# SANE_v1.net
KiCad netlist of a schematic drawn in EAGLE
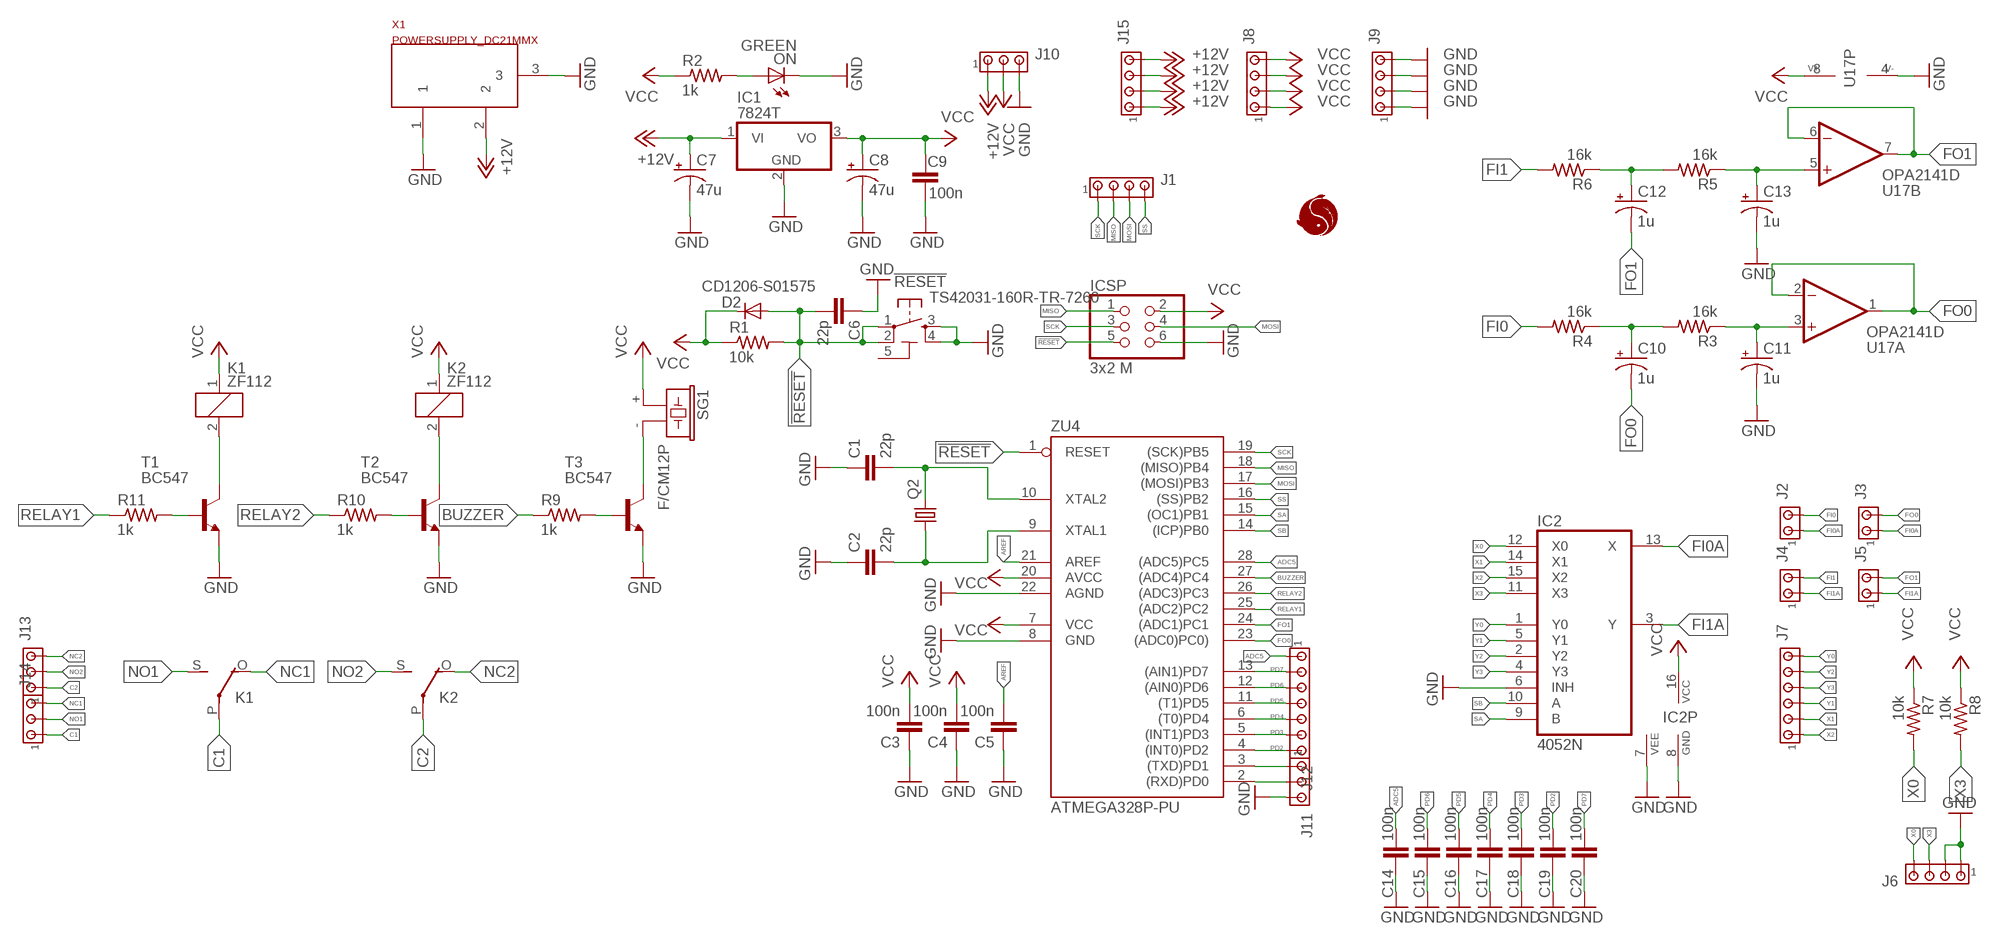
[diagram p0: schematic, sheet 1]

(export (version "E")
  (design (tool "Eeschema 10.0.6"))
  (components
    (comp (ref "!RESET")
      (value "TS42031-160R-TR-7260")
      (footprint "eagle-import:TS42")
      (libsource (lib "eagle-import") (part "TS42"))
    )
    (comp (ref "C1")
      (value "22p")
      (footprint "eagle-import:C0805")
      (libsource (lib "eagle-import") (part "C-EUC0805"))
    )
    (comp (ref "C2")
      (value "22p")
      (footprint "eagle-import:C0805")
      (libsource (lib "eagle-import") (part "C-EUC0805"))
    )
    (comp (ref "C3")
      (value "100n")
      (footprint "eagle-import:C0805")
      (libsource (lib "eagle-import") (part "C-EUC0805"))
    )
    (comp (ref "C4")
      (value "100n")
      (footprint "eagle-import:C0805")
      (libsource (lib "eagle-import") (part "C-EUC0805"))
    )
    (comp (ref "C5")
      (value "100n")
      (footprint "eagle-import:C0805")
      (libsource (lib "eagle-import") (part "C-EUC0805"))
    )
    (comp (ref "C6")
      (value "22p")
      (footprint "eagle-import:C0805")
      (libsource (lib "eagle-import") (part "C-EUC0805"))
    )
    (comp (ref "C7")
      (value "47u")
      (footprint "eagle-import:E2-4")
      (libsource (lib "eagle-import") (part "CPOL-USE2-4"))
    )
    (comp (ref "C8")
      (value "47u")
      (footprint "eagle-import:E2-4")
      (libsource (lib "eagle-import") (part "CPOL-USE2-4"))
    )
    (comp (ref "C9")
      (value "100n")
      (footprint "eagle-import:C0805")
      (libsource (lib "eagle-import") (part "C-EUC0805"))
    )
    (comp (ref "C10")
      (value "1u")
      (footprint "eagle-import:E2-4")
      (libsource (lib "eagle-import") (part "CPOL-USE2-4"))
    )
    (comp (ref "C11")
      (value "1u")
      (footprint "eagle-import:E2-4")
      (libsource (lib "eagle-import") (part "CPOL-USE2-4"))
    )
    (comp (ref "C12")
      (value "1u")
      (footprint "eagle-import:E2-4")
      (libsource (lib "eagle-import") (part "CPOL-USE2-4"))
    )
    (comp (ref "C13")
      (value "1u")
      (footprint "eagle-import:E2-4")
      (libsource (lib "eagle-import") (part "CPOL-USE2-4"))
    )
    (comp (ref "C14")
      (value "100n")
      (footprint "eagle-import:C0805")
      (libsource (lib "eagle-import") (part "C-EUC0805"))
    )
    (comp (ref "C15")
      (value "100n")
      (footprint "eagle-import:C0805")
      (libsource (lib "eagle-import") (part "C-EUC0805"))
    )
    (comp (ref "C16")
      (value "100n")
      (footprint "eagle-import:C0805")
      (libsource (lib "eagle-import") (part "C-EUC0805"))
    )
    (comp (ref "C17")
      (value "100n")
      (footprint "eagle-import:C0805")
      (libsource (lib "eagle-import") (part "C-EUC0805"))
    )
    (comp (ref "C18")
      (value "100n")
      (footprint "eagle-import:C0805")
      (libsource (lib "eagle-import") (part "C-EUC0805"))
    )
    (comp (ref "C19")
      (value "100n")
      (footprint "eagle-import:C0805")
      (libsource (lib "eagle-import") (part "C-EUC0805"))
    )
    (comp (ref "C20")
      (value "100n")
      (footprint "eagle-import:C0805")
      (libsource (lib "eagle-import") (part "C-EUC0805"))
    )
    (comp (ref "D2")
      (value "CD1206-S01575")
      (footprint "eagle-import:MINIMELF")
      (libsource (lib "eagle-import") (part "DIODE-MINIMELF"))
    )
    (comp (ref "IC1")
      (value "7824T")
      (footprint "eagle-import:TO220H")
      (libsource (lib "eagle-import") (part "78T24"))
    )
    (comp (ref "IC2")
      (value "4052N")
      (footprint "eagle-import:DIL16")
      (libsource (lib "eagle-import") (part "4052N"))
    )
    (comp (ref "ICSP")
      (value "3x2 M")
      (footprint "eagle-import:2X03")
      (libsource (lib "eagle-import") (part "PINHD-2X3"))
    )
    (comp (ref "J1")
      (value "MTA04-100")
      (footprint "eagle-import:10X04MTA")
      (libsource (lib "eagle-import") (part "MTA04-100"))
    )
    (comp (ref "J2")
      (value "MTA02-100")
      (footprint "eagle-import:10X02MTA")
      (libsource (lib "eagle-import") (part "MTA02-100"))
    )
    (comp (ref "J3")
      (value "MTA02-100")
      (footprint "eagle-import:10X02MTA")
      (libsource (lib "eagle-import") (part "MTA02-100"))
    )
    (comp (ref "J4")
      (value "MTA02-100")
      (footprint "eagle-import:10X02MTA")
      (libsource (lib "eagle-import") (part "MTA02-100"))
    )
    (comp (ref "J5")
      (value "MTA02-100")
      (footprint "eagle-import:10X02MTA")
      (libsource (lib "eagle-import") (part "MTA02-100"))
    )
    (comp (ref "J6")
      (value "MTA04-100")
      (footprint "eagle-import:10X04MTA")
      (libsource (lib "eagle-import") (part "MTA04-100"))
    )
    (comp (ref "J7")
      (value "MTA06-100")
      (footprint "eagle-import:10X06MTA")
      (libsource (lib "eagle-import") (part "MTA06-100"))
    )
    (comp (ref "J8")
      (value "MTA04-100")
      (footprint "eagle-import:10X04MTA")
      (libsource (lib "eagle-import") (part "MTA04-100"))
    )
    (comp (ref "J9")
      (value "MTA04-100")
      (footprint "eagle-import:10X04MTA")
      (libsource (lib "eagle-import") (part "MTA04-100"))
    )
    (comp (ref "J10")
      (value "MTA03-100")
      (footprint "eagle-import:10X03MTA")
      (libsource (lib "eagle-import") (part "MTA03-100"))
    )
    (comp (ref "J11")
      (value "MTA03-100")
      (footprint "eagle-import:10X03MTA")
      (libsource (lib "eagle-import") (part "MTA03-100"))
    )
    (comp (ref "J12")
      (value "MTA07-100")
      (footprint "eagle-import:10X07MTA")
      (libsource (lib "eagle-import") (part "MTA07-100"))
    )
    (comp (ref "J13")
      (value "MTA03-156")
      (footprint "eagle-import:1X3MTA")
      (libsource (lib "eagle-import") (part "MTA03-156"))
    )
    (comp (ref "J14")
      (value "MTA03-156")
      (footprint "eagle-import:1X3MTA")
      (libsource (lib "eagle-import") (part "MTA03-156"))
    )
    (comp (ref "J15")
      (value "MTA04-100")
      (footprint "eagle-import:10X04MTA")
      (libsource (lib "eagle-import") (part "MTA04-100"))
    )
    (comp (ref "K1")
      (value "ZF112")
      (footprint "eagle-import:ZF112")
      (libsource (lib "eagle-import") (part "ZF112"))
    )
    (comp (ref "K2")
      (value "ZF112")
      (footprint "eagle-import:ZF112")
      (libsource (lib "eagle-import") (part "ZF112"))
    )
    (comp (ref "ON")
      (value "GREEN")
      (footprint "eagle-import:CHIP-LED0805")
      (libsource (lib "eagle-import") (part "LEDCHIP-LED0805"))
    )
    (comp (ref "Q2")
      (value "CRYSTALHC49U-V")
      (footprint "eagle-import:HC49U-V")
      (libsource (lib "eagle-import") (part "CRYSTALHC49U-V"))
    )
    (comp (ref "R1")
      (value "10k")
      (footprint "eagle-import:R0805")
      (libsource (lib "eagle-import") (part "R-US_R0805"))
    )
    (comp (ref "R2")
      (value "1k")
      (footprint "eagle-import:R0805")
      (libsource (lib "eagle-import") (part "R-US_R0805"))
    )
    (comp (ref "R3")
      (value "16k")
      (footprint "eagle-import:R0805")
      (libsource (lib "eagle-import") (part "R-US_R0805"))
    )
    (comp (ref "R4")
      (value "16k")
      (footprint "eagle-import:R0805")
      (libsource (lib "eagle-import") (part "R-US_R0805"))
    )
    (comp (ref "R5")
      (value "16k")
      (footprint "eagle-import:R0805")
      (libsource (lib "eagle-import") (part "R-US_R0805"))
    )
    (comp (ref "R6")
      (value "16k")
      (footprint "eagle-import:R0805")
      (libsource (lib "eagle-import") (part "R-US_R0805"))
    )
    (comp (ref "R7")
      (value "10k")
      (footprint "eagle-import:R0805")
      (libsource (lib "eagle-import") (part "R-US_R0805"))
    )
    (comp (ref "R8")
      (value "10k")
      (footprint "eagle-import:R0805")
      (libsource (lib "eagle-import") (part "R-US_R0805"))
    )
    (comp (ref "R9")
      (value "1k")
      (footprint "eagle-import:R0805")
      (libsource (lib "eagle-import") (part "R-US_R0805"))
    )
    (comp (ref "R10")
      (value "1k")
      (footprint "eagle-import:R0805")
      (libsource (lib "eagle-import") (part "R-US_R0805"))
    )
    (comp (ref "R11")
      (value "1k")
      (footprint "eagle-import:R0805")
      (libsource (lib "eagle-import") (part "R-US_R0805"))
    )
    (comp (ref "SG1")
      (value "F/CM12P")
      (footprint "eagle-import:F_CM12P")
      (libsource (lib "eagle-import") (part "F/CM12P"))
    )
    (comp (ref "T1")
      (value "BC547")
      (footprint "eagle-import:TO92")
      (libsource (lib "eagle-import") (part "BC547"))
    )
    (comp (ref "T2")
      (value "BC547")
      (footprint "eagle-import:TO92")
      (libsource (lib "eagle-import") (part "BC547"))
    )
    (comp (ref "T3")
      (value "BC547")
      (footprint "eagle-import:TO92")
      (libsource (lib "eagle-import") (part "BC547"))
    )
    (comp (ref "U$1")
      (value "LOGO-SANE")
      (footprint "eagle-import:LOGO-SANE")
      (libsource (lib "eagle-import") (part "LOGO-SANE"))
    )
    (comp (ref "U17")
      (value "OPA2141D")
      (footprint "eagle-import:SO08")
      (libsource (lib "eagle-import") (part "OPA2141D"))
    )
    (comp (ref "X1")
      (value "POWERSUPPLY_DC21MMX")
      (footprint "eagle-import:POWERSUPPLY_DC-21MM")
      (libsource (lib "eagle-import") (part "POWERSUPPLY_DC21MMX"))
    )
    (comp (ref "ZU4")
      (value "ATMEGA328P-PU")
      (footprint "eagle-import:DIL28-3")
      (libsource (lib "eagle-import") (part "ATMEGA328P-PU"))
    )
  )
  (nets
    (net (code "1") (name "+12V") (class "Default")
      (node (ref "C7") (pin "+") (pinfunction "+_+") (pintype "passive"))
      (node (ref "IC1") (pin "1") (pinfunction "VI_1") (pintype "input"))
      (node (ref "J10") (pin "1") (pinfunction "1_1") (pintype "passive"))
      (node (ref "J15") (pin "1") (pinfunction "1_1") (pintype "passive"))
      (node (ref "J15") (pin "2") (pinfunction "2_2") (pintype "passive"))
      (node (ref "J15") (pin "3") (pinfunction "3_3") (pintype "passive"))
      (node (ref "J15") (pin "4") (pinfunction "4_4") (pintype "passive"))
      (node (ref "X1") (pin "2") (pinfunction "2_2") (pintype "power_in"))
    )
    (net (code "2") (name "/5-GND") (class "Default")
      (node (ref "!RESET") (pin "5") (pinfunction "5-GND_5") (pintype "power_in"))
    )
    (net (code "3") (name "/~{RESET}") (class "Default")
      (node (ref "!RESET") (pin "1") (pinfunction "1_1") (pintype "passive"))
      (node (ref "!RESET") (pin "2") (pinfunction "2_2") (pintype "passive"))
      (node (ref "C6") (pin "2") (pinfunction "2_2") (pintype "passive"))
      (node (ref "D2") (pin "A") (pinfunction "A_A") (pintype "passive"))
      (node (ref "ICSP") (pin "5") (pinfunction "5_5") (pintype "passive"))
      (node (ref "R1") (pin "2") (pinfunction "2_2") (pintype "passive"))
      (node (ref "ZU4") (pin "1") (pinfunction "RESET_1") (pintype "input"))
    )
    (net (code "4") (name "ADC5") (class "Default")
      (node (ref "C14") (pin "2") (pinfunction "2_2") (pintype "passive"))
      (node (ref "J12") (pin "1") (pinfunction "1_1") (pintype "passive"))
      (node (ref "ZU4") (pin "28") (pinfunction "(ADC5)PC5_28") (pintype "bidirectional"))
    )
    (net (code "5") (name "AREF") (class "Default")
      (node (ref "C5") (pin "2") (pinfunction "2_2") (pintype "passive"))
      (node (ref "ZU4") (pin "21") (pinfunction "AREF_21") (pintype "passive"))
    )
    (net (code "6") (name "BUZZER") (class "Default")
      (node (ref "R9") (pin "1") (pinfunction "1_1") (pintype "passive"))
      (node (ref "ZU4") (pin "27") (pinfunction "(ADC4)PC4_27") (pintype "bidirectional"))
    )
    (net (code "7") (name "C1") (class "Default")
      (node (ref "J14") (pin "1") (pinfunction "1_1") (pintype "passive"))
      (node (ref "K1") (pin "P") (pinfunction "P_P") (pintype "passive"))
    )
    (net (code "8") (name "C2") (class "Default")
      (node (ref "J13") (pin "1") (pinfunction "1_1") (pintype "passive"))
      (node (ref "K2") (pin "P") (pinfunction "P_P") (pintype "passive"))
    )
    (net (code "9") (name "FI0") (class "Default")
      (node (ref "J2") (pin "2") (pinfunction "2_2") (pintype "passive"))
      (node (ref "R4") (pin "2") (pinfunction "2_2") (pintype "passive"))
    )
    (net (code "10") (name "FI0A") (class "Default")
      (node (ref "IC2") (pin "13") (pinfunction "X_13") (pintype "bidirectional"))
      (node (ref "J2") (pin "1") (pinfunction "1_1") (pintype "passive"))
      (node (ref "J3") (pin "1") (pinfunction "1_1") (pintype "passive"))
    )
    (net (code "11") (name "FI1") (class "Default")
      (node (ref "J4") (pin "2") (pinfunction "2_2") (pintype "passive"))
      (node (ref "R6") (pin "2") (pinfunction "2_2") (pintype "passive"))
    )
    (net (code "12") (name "FI1A") (class "Default")
      (node (ref "IC2") (pin "3") (pinfunction "Y_3") (pintype "bidirectional"))
      (node (ref "J4") (pin "1") (pinfunction "1_1") (pintype "passive"))
      (node (ref "J5") (pin "1") (pinfunction "1_1") (pintype "passive"))
    )
    (net (code "13") (name "FO0") (class "Default")
      (node (ref "C10") (pin "-") (pinfunction "-_-") (pintype "passive"))
      (node (ref "J3") (pin "2") (pinfunction "2_2") (pintype "passive"))
      (node (ref "U17") (pin "1") (pinfunction "OUT_1") (pintype "output"))
      (node (ref "U17") (pin "2") (pinfunction "-IN_2") (pintype "input"))
      (node (ref "ZU4") (pin "23") (pinfunction "(ADC0)PC0)_23") (pintype "bidirectional"))
    )
    (net (code "14") (name "FO1") (class "Default")
      (node (ref "C12") (pin "-") (pinfunction "-_-") (pintype "passive"))
      (node (ref "J5") (pin "2") (pinfunction "2_2") (pintype "passive"))
      (node (ref "U17") (pin "6") (pinfunction "-IN_6") (pintype "input"))
      (node (ref "U17") (pin "7") (pinfunction "OUT_7") (pintype "output"))
      (node (ref "ZU4") (pin "24") (pinfunction "(ADC1)PC1_24") (pintype "bidirectional"))
    )
    (net (code "15") (name "GND") (class "Default")
      (node (ref "!RESET") (pin "3") (pinfunction "3_3") (pintype "passive"))
      (node (ref "!RESET") (pin "4") (pinfunction "4_4") (pintype "passive"))
      (node (ref "C1") (pin "1") (pinfunction "1_1") (pintype "passive"))
      (node (ref "C11") (pin "-") (pinfunction "-_-") (pintype "passive"))
      (node (ref "C13") (pin "-") (pinfunction "-_-") (pintype "passive"))
      (node (ref "C14") (pin "1") (pinfunction "1_1") (pintype "passive"))
      (node (ref "C15") (pin "1") (pinfunction "1_1") (pintype "passive"))
      (node (ref "C16") (pin "1") (pinfunction "1_1") (pintype "passive"))
      (node (ref "C17") (pin "1") (pinfunction "1_1") (pintype "passive"))
      (node (ref "C18") (pin "1") (pinfunction "1_1") (pintype "passive"))
      (node (ref "C19") (pin "1") (pinfunction "1_1") (pintype "passive"))
      (node (ref "C2") (pin "1") (pinfunction "1_1") (pintype "passive"))
      (node (ref "C20") (pin "1") (pinfunction "1_1") (pintype "passive"))
      (node (ref "C3") (pin "1") (pinfunction "1_1") (pintype "passive"))
      (node (ref "C4") (pin "1") (pinfunction "1_1") (pintype "passive"))
      (node (ref "C5") (pin "1") (pinfunction "1_1") (pintype "passive"))
      (node (ref "C6") (pin "1") (pinfunction "1_1") (pintype "passive"))
      (node (ref "C7") (pin "-") (pinfunction "-_-") (pintype "passive"))
      (node (ref "C8") (pin "-") (pinfunction "-_-") (pintype "passive"))
      (node (ref "C9") (pin "1") (pinfunction "1_1") (pintype "passive"))
      (node (ref "IC1") (pin "2") (pinfunction "GND_2") (pintype "passive"))
      (node (ref "IC2") (pin "6") (pinfunction "INH_6") (pintype "input"))
      (node (ref "IC2") (pin "7") (pinfunction "VEE_7") (pintype "power_in"))
      (node (ref "IC2") (pin "8") (pinfunction "GND_8") (pintype "power_in"))
      (node (ref "ICSP") (pin "6") (pinfunction "6_6") (pintype "passive"))
      (node (ref "J10") (pin "3") (pinfunction "3_3") (pintype "passive"))
      (node (ref "J11") (pin "3") (pinfunction "3_3") (pintype "passive"))
      (node (ref "J6") (pin "1") (pinfunction "1_1") (pintype "passive"))
      (node (ref "J6") (pin "2") (pinfunction "2_2") (pintype "passive"))
      (node (ref "J9") (pin "1") (pinfunction "1_1") (pintype "passive"))
      (node (ref "J9") (pin "2") (pinfunction "2_2") (pintype "passive"))
      (node (ref "J9") (pin "3") (pinfunction "3_3") (pintype "passive"))
      (node (ref "J9") (pin "4") (pinfunction "4_4") (pintype "passive"))
      (node (ref "ON") (pin "C") (pinfunction "C_C") (pintype "passive"))
      (node (ref "T1") (pin "1") (pinfunction "E_1") (pintype "passive"))
      (node (ref "T2") (pin "1") (pinfunction "E_1") (pintype "passive"))
      (node (ref "T3") (pin "1") (pinfunction "E_1") (pintype "passive"))
      (node (ref "U17") (pin "4") (pinfunction "V-_4") (pintype "power_in"))
      (node (ref "X1") (pin "1") (pinfunction "1_1") (pintype "power_in"))
      (node (ref "X1") (pin "3") (pinfunction "3_3") (pintype "power_in"))
      (node (ref "ZU4") (pin "22") (pinfunction "AGND_22") (pintype "power_in"))
      (node (ref "ZU4") (pin "8") (pinfunction "GND_8") (pintype "power_in"))
    )
    (net (code "16") (name "MISO") (class "Default")
      (node (ref "ICSP") (pin "1") (pinfunction "1_1") (pintype "passive"))
      (node (ref "J1") (pin "2") (pinfunction "2_2") (pintype "passive"))
      (node (ref "ZU4") (pin "18") (pinfunction "(MISO)PB4_18") (pintype "bidirectional"))
    )
    (net (code "17") (name "MOSI") (class "Default")
      (node (ref "ICSP") (pin "4") (pinfunction "4_4") (pintype "passive"))
      (node (ref "J1") (pin "3") (pinfunction "3_3") (pintype "passive"))
      (node (ref "ZU4") (pin "17") (pinfunction "(MOSI)PB3_17") (pintype "bidirectional"))
    )
    (net (code "18") (name "NC1") (class "Default")
      (node (ref "J14") (pin "3") (pinfunction "3_3") (pintype "passive"))
      (node (ref "K1") (pin "O") (pinfunction "O_O") (pintype "passive"))
    )
    (net (code "19") (name "NC2") (class "Default")
      (node (ref "J13") (pin "3") (pinfunction "3_3") (pintype "passive"))
      (node (ref "K2") (pin "O") (pinfunction "O_O") (pintype "passive"))
    )
    (net (code "20") (name "NO1") (class "Default")
      (node (ref "J14") (pin "2") (pinfunction "2_2") (pintype "passive"))
      (node (ref "K1") (pin "S") (pinfunction "S_S") (pintype "passive"))
    )
    (net (code "21") (name "NO2") (class "Default")
      (node (ref "J13") (pin "2") (pinfunction "2_2") (pintype "passive"))
      (node (ref "K2") (pin "S") (pinfunction "S_S") (pintype "passive"))
    )
    (net (code "22") (name "Net-(C10-Pad+)") (class "Default")
      (node (ref "C10") (pin "+") (pinfunction "+_+") (pintype "passive"))
      (node (ref "R3") (pin "2") (pinfunction "2_2") (pintype "passive"))
      (node (ref "R4") (pin "1") (pinfunction "1_1") (pintype "passive"))
    )
    (net (code "23") (name "Net-(C12-Pad+)") (class "Default")
      (node (ref "C12") (pin "+") (pinfunction "+_+") (pintype "passive"))
      (node (ref "R5") (pin "2") (pinfunction "2_2") (pintype "passive"))
      (node (ref "R6") (pin "1") (pinfunction "1_1") (pintype "passive"))
    )
    (net (code "24") (name "Net-(ON-PadA)") (class "Default")
      (node (ref "ON") (pin "A") (pinfunction "A_A") (pintype "passive"))
      (node (ref "R2") (pin "2") (pinfunction "2_2") (pintype "passive"))
    )
    (net (code "25") (name "Net-(SG1-2)") (class "Default")
      (node (ref "SG1") (pin "-") (pinfunction "2_-") (pintype "passive"))
      (node (ref "T3") (pin "3") (pinfunction "C_3") (pintype "passive"))
    )
    (net (code "26") (name "Net-(T1-B)") (class "Default")
      (node (ref "R11") (pin "2") (pinfunction "2_2") (pintype "passive"))
      (node (ref "T1") (pin "2") (pinfunction "B_2") (pintype "passive"))
    )
    (net (code "27") (name "Net-(T1-C)") (class "Default")
      (node (ref "K1") (pin "2") (pinfunction "2_2") (pintype "passive"))
      (node (ref "T1") (pin "3") (pinfunction "C_3") (pintype "passive"))
    )
    (net (code "28") (name "Net-(T2-B)") (class "Default")
      (node (ref "R10") (pin "2") (pinfunction "2_2") (pintype "passive"))
      (node (ref "T2") (pin "2") (pinfunction "B_2") (pintype "passive"))
    )
    (net (code "29") (name "Net-(T2-C)") (class "Default")
      (node (ref "K2") (pin "2") (pinfunction "2_2") (pintype "passive"))
      (node (ref "T2") (pin "3") (pinfunction "C_3") (pintype "passive"))
    )
    (net (code "30") (name "Net-(T3-B)") (class "Default")
      (node (ref "R9") (pin "2") (pinfunction "2_2") (pintype "passive"))
      (node (ref "T3") (pin "2") (pinfunction "B_2") (pintype "passive"))
    )
    (net (code "31") (name "Net-(U17A-+IN)") (class "Default")
      (node (ref "C11") (pin "+") (pinfunction "+_+") (pintype "passive"))
      (node (ref "R3") (pin "1") (pinfunction "1_1") (pintype "passive"))
      (node (ref "U17") (pin "3") (pinfunction "+IN_3") (pintype "input"))
    )
    (net (code "32") (name "Net-(U17B-+IN)") (class "Default")
      (node (ref "C13") (pin "+") (pinfunction "+_+") (pintype "passive"))
      (node (ref "R5") (pin "1") (pinfunction "1_1") (pintype "passive"))
      (node (ref "U17") (pin "5") (pinfunction "+IN_5") (pintype "input"))
    )
    (net (code "33") (name "Net-(ZU4-(RXD)PD0)") (class "Default")
      (node (ref "J11") (pin "2") (pinfunction "2_2") (pintype "passive"))
      (node (ref "ZU4") (pin "2") (pinfunction "(RXD)PD0_2") (pintype "bidirectional"))
    )
    (net (code "34") (name "Net-(ZU4-(TXD)PD1)") (class "Default")
      (node (ref "J11") (pin "1") (pinfunction "1_1") (pintype "passive"))
      (node (ref "ZU4") (pin "3") (pinfunction "(TXD)PD1_3") (pintype "bidirectional"))
    )
    (net (code "35") (name "Net-(ZU4-XTAL1)") (class "Default")
      (node (ref "C2") (pin "2") (pinfunction "2_2") (pintype "passive"))
      (node (ref "Q2") (pin "1") (pinfunction "1_1") (pintype "passive"))
      (node (ref "ZU4") (pin "9") (pinfunction "XTAL1_9") (pintype "bidirectional"))
    )
    (net (code "36") (name "Net-(ZU4-XTAL2)") (class "Default")
      (node (ref "C1") (pin "2") (pinfunction "2_2") (pintype "passive"))
      (node (ref "Q2") (pin "2") (pinfunction "2_2") (pintype "passive"))
      (node (ref "ZU4") (pin "10") (pinfunction "XTAL2_10") (pintype "bidirectional"))
    )
    (net (code "37") (name "PD2") (class "Default")
      (node (ref "C19") (pin "2") (pinfunction "2_2") (pintype "passive"))
      (node (ref "J12") (pin "7") (pinfunction "7_7") (pintype "passive"))
      (node (ref "ZU4") (pin "4") (pinfunction "(INT0)PD2_4") (pintype "bidirectional"))
    )
    (net (code "38") (name "PD3") (class "Default")
      (node (ref "C18") (pin "2") (pinfunction "2_2") (pintype "passive"))
      (node (ref "J12") (pin "6") (pinfunction "6_6") (pintype "passive"))
      (node (ref "ZU4") (pin "5") (pinfunction "(INT1)PD3_5") (pintype "bidirectional"))
    )
    (net (code "39") (name "PD4") (class "Default")
      (node (ref "C17") (pin "2") (pinfunction "2_2") (pintype "passive"))
      (node (ref "J12") (pin "5") (pinfunction "5_5") (pintype "passive"))
      (node (ref "ZU4") (pin "6") (pinfunction "(T0)PD4_6") (pintype "bidirectional"))
    )
    (net (code "40") (name "PD5") (class "Default")
      (node (ref "C16") (pin "2") (pinfunction "2_2") (pintype "passive"))
      (node (ref "J12") (pin "4") (pinfunction "4_4") (pintype "passive"))
      (node (ref "ZU4") (pin "11") (pinfunction "(T1)PD5_11") (pintype "bidirectional"))
    )
    (net (code "41") (name "PD6") (class "Default")
      (node (ref "C15") (pin "2") (pinfunction "2_2") (pintype "passive"))
      (node (ref "J12") (pin "3") (pinfunction "3_3") (pintype "passive"))
      (node (ref "ZU4") (pin "12") (pinfunction "(AIN0)PD6_12") (pintype "bidirectional"))
    )
    (net (code "42") (name "PD7") (class "Default")
      (node (ref "C20") (pin "2") (pinfunction "2_2") (pintype "passive"))
      (node (ref "J12") (pin "2") (pinfunction "2_2") (pintype "passive"))
      (node (ref "ZU4") (pin "13") (pinfunction "(AIN1)PD7_13") (pintype "bidirectional"))
    )
    (net (code "43") (name "RELAY1") (class "Default")
      (node (ref "R11") (pin "1") (pinfunction "1_1") (pintype "passive"))
      (node (ref "ZU4") (pin "25") (pinfunction "(ADC2)PC2_25") (pintype "bidirectional"))
    )
    (net (code "44") (name "RELAY2") (class "Default")
      (node (ref "R10") (pin "1") (pinfunction "1_1") (pintype "passive"))
      (node (ref "ZU4") (pin "26") (pinfunction "(ADC3)PC3_26") (pintype "bidirectional"))
    )
    (net (code "45") (name "SA") (class "Default")
      (node (ref "IC2") (pin "9") (pinfunction "B_9") (pintype "input"))
      (node (ref "ZU4") (pin "15") (pinfunction "(OC1)PB1_15") (pintype "bidirectional"))
    )
    (net (code "46") (name "SB") (class "Default")
      (node (ref "IC2") (pin "10") (pinfunction "A_10") (pintype "input"))
      (node (ref "ZU4") (pin "14") (pinfunction "(ICP)PB0_14") (pintype "bidirectional"))
    )
    (net (code "47") (name "SCK") (class "Default")
      (node (ref "ICSP") (pin "3") (pinfunction "3_3") (pintype "passive"))
      (node (ref "J1") (pin "1") (pinfunction "1_1") (pintype "passive"))
      (node (ref "ZU4") (pin "19") (pinfunction "(SCK)PB5_19") (pintype "bidirectional"))
    )
    (net (code "48") (name "SS") (class "Default")
      (node (ref "J1") (pin "4") (pinfunction "4_4") (pintype "passive"))
      (node (ref "ZU4") (pin "16") (pinfunction "(SS)PB2_16") (pintype "bidirectional"))
    )
    (net (code "49") (name "VCC") (class "Default")
      (node (ref "C3") (pin "2") (pinfunction "2_2") (pintype "passive"))
      (node (ref "C4") (pin "2") (pinfunction "2_2") (pintype "passive"))
      (node (ref "C8") (pin "+") (pinfunction "+_+") (pintype "passive"))
      (node (ref "C9") (pin "2") (pinfunction "2_2") (pintype "passive"))
      (node (ref "D2") (pin "C") (pinfunction "C_C") (pintype "passive"))
      (node (ref "IC1") (pin "3") (pinfunction "VO_3") (pintype "passive"))
      (node (ref "IC2") (pin "16") (pinfunction "VCC_16") (pintype "power_in"))
      (node (ref "ICSP") (pin "2") (pinfunction "2_2") (pintype "passive"))
      (node (ref "J10") (pin "2") (pinfunction "2_2") (pintype "passive"))
      (node (ref "J8") (pin "1") (pinfunction "1_1") (pintype "passive"))
      (node (ref "J8") (pin "2") (pinfunction "2_2") (pintype "passive"))
      (node (ref "J8") (pin "3") (pinfunction "3_3") (pintype "passive"))
      (node (ref "J8") (pin "4") (pinfunction "4_4") (pintype "passive"))
      (node (ref "K1") (pin "1") (pinfunction "1_1") (pintype "passive"))
      (node (ref "K2") (pin "1") (pinfunction "1_1") (pintype "passive"))
      (node (ref "R1") (pin "1") (pinfunction "1_1") (pintype "passive"))
      (node (ref "R2") (pin "1") (pinfunction "1_1") (pintype "passive"))
      (node (ref "R7") (pin "1") (pinfunction "1_1") (pintype "passive"))
      (node (ref "R8") (pin "1") (pinfunction "1_1") (pintype "passive"))
      (node (ref "SG1") (pin "+") (pinfunction "1_+") (pintype "passive"))
      (node (ref "U17") (pin "8") (pinfunction "V+_8") (pintype "power_in"))
      (node (ref "ZU4") (pin "20") (pinfunction "AVCC_20") (pintype "power_in"))
      (node (ref "ZU4") (pin "7") (pinfunction "VCC_7") (pintype "power_in"))
    )
    (net (code "50") (name "X0") (class "Default")
      (node (ref "IC2") (pin "12") (pinfunction "X0_12") (pintype "bidirectional"))
      (node (ref "J6") (pin "4") (pinfunction "4_4") (pintype "passive"))
      (node (ref "R7") (pin "2") (pinfunction "2_2") (pintype "passive"))
    )
    (net (code "51") (name "X1") (class "Default")
      (node (ref "IC2") (pin "14") (pinfunction "X1_14") (pintype "bidirectional"))
      (node (ref "J7") (pin "2") (pinfunction "2_2") (pintype "passive"))
    )
    (net (code "52") (name "X2") (class "Default")
      (node (ref "IC2") (pin "15") (pinfunction "X2_15") (pintype "bidirectional"))
      (node (ref "J7") (pin "1") (pinfunction "1_1") (pintype "passive"))
    )
    (net (code "53") (name "X3") (class "Default")
      (node (ref "IC2") (pin "11") (pinfunction "X3_11") (pintype "bidirectional"))
      (node (ref "J6") (pin "3") (pinfunction "3_3") (pintype "passive"))
      (node (ref "R8") (pin "2") (pinfunction "2_2") (pintype "passive"))
    )
    (net (code "54") (name "Y0") (class "Default")
      (node (ref "IC2") (pin "1") (pinfunction "Y0_1") (pintype "bidirectional"))
      (node (ref "J7") (pin "6") (pinfunction "6_6") (pintype "passive"))
    )
    (net (code "55") (name "Y1") (class "Default")
      (node (ref "IC2") (pin "5") (pinfunction "Y1_5") (pintype "bidirectional"))
      (node (ref "J7") (pin "3") (pinfunction "3_3") (pintype "passive"))
    )
    (net (code "56") (name "Y2") (class "Default")
      (node (ref "IC2") (pin "2") (pinfunction "Y2_2") (pintype "bidirectional"))
      (node (ref "J7") (pin "5") (pinfunction "5_5") (pintype "passive"))
    )
    (net (code "57") (name "Y3") (class "Default")
      (node (ref "IC2") (pin "4") (pinfunction "Y3_4") (pintype "bidirectional"))
      (node (ref "J7") (pin "4") (pinfunction "4_4") (pintype "passive"))
    )
  )
)
